# Digital_OUT.net
KiCad netlist of a schematic drawn in Altium Designer
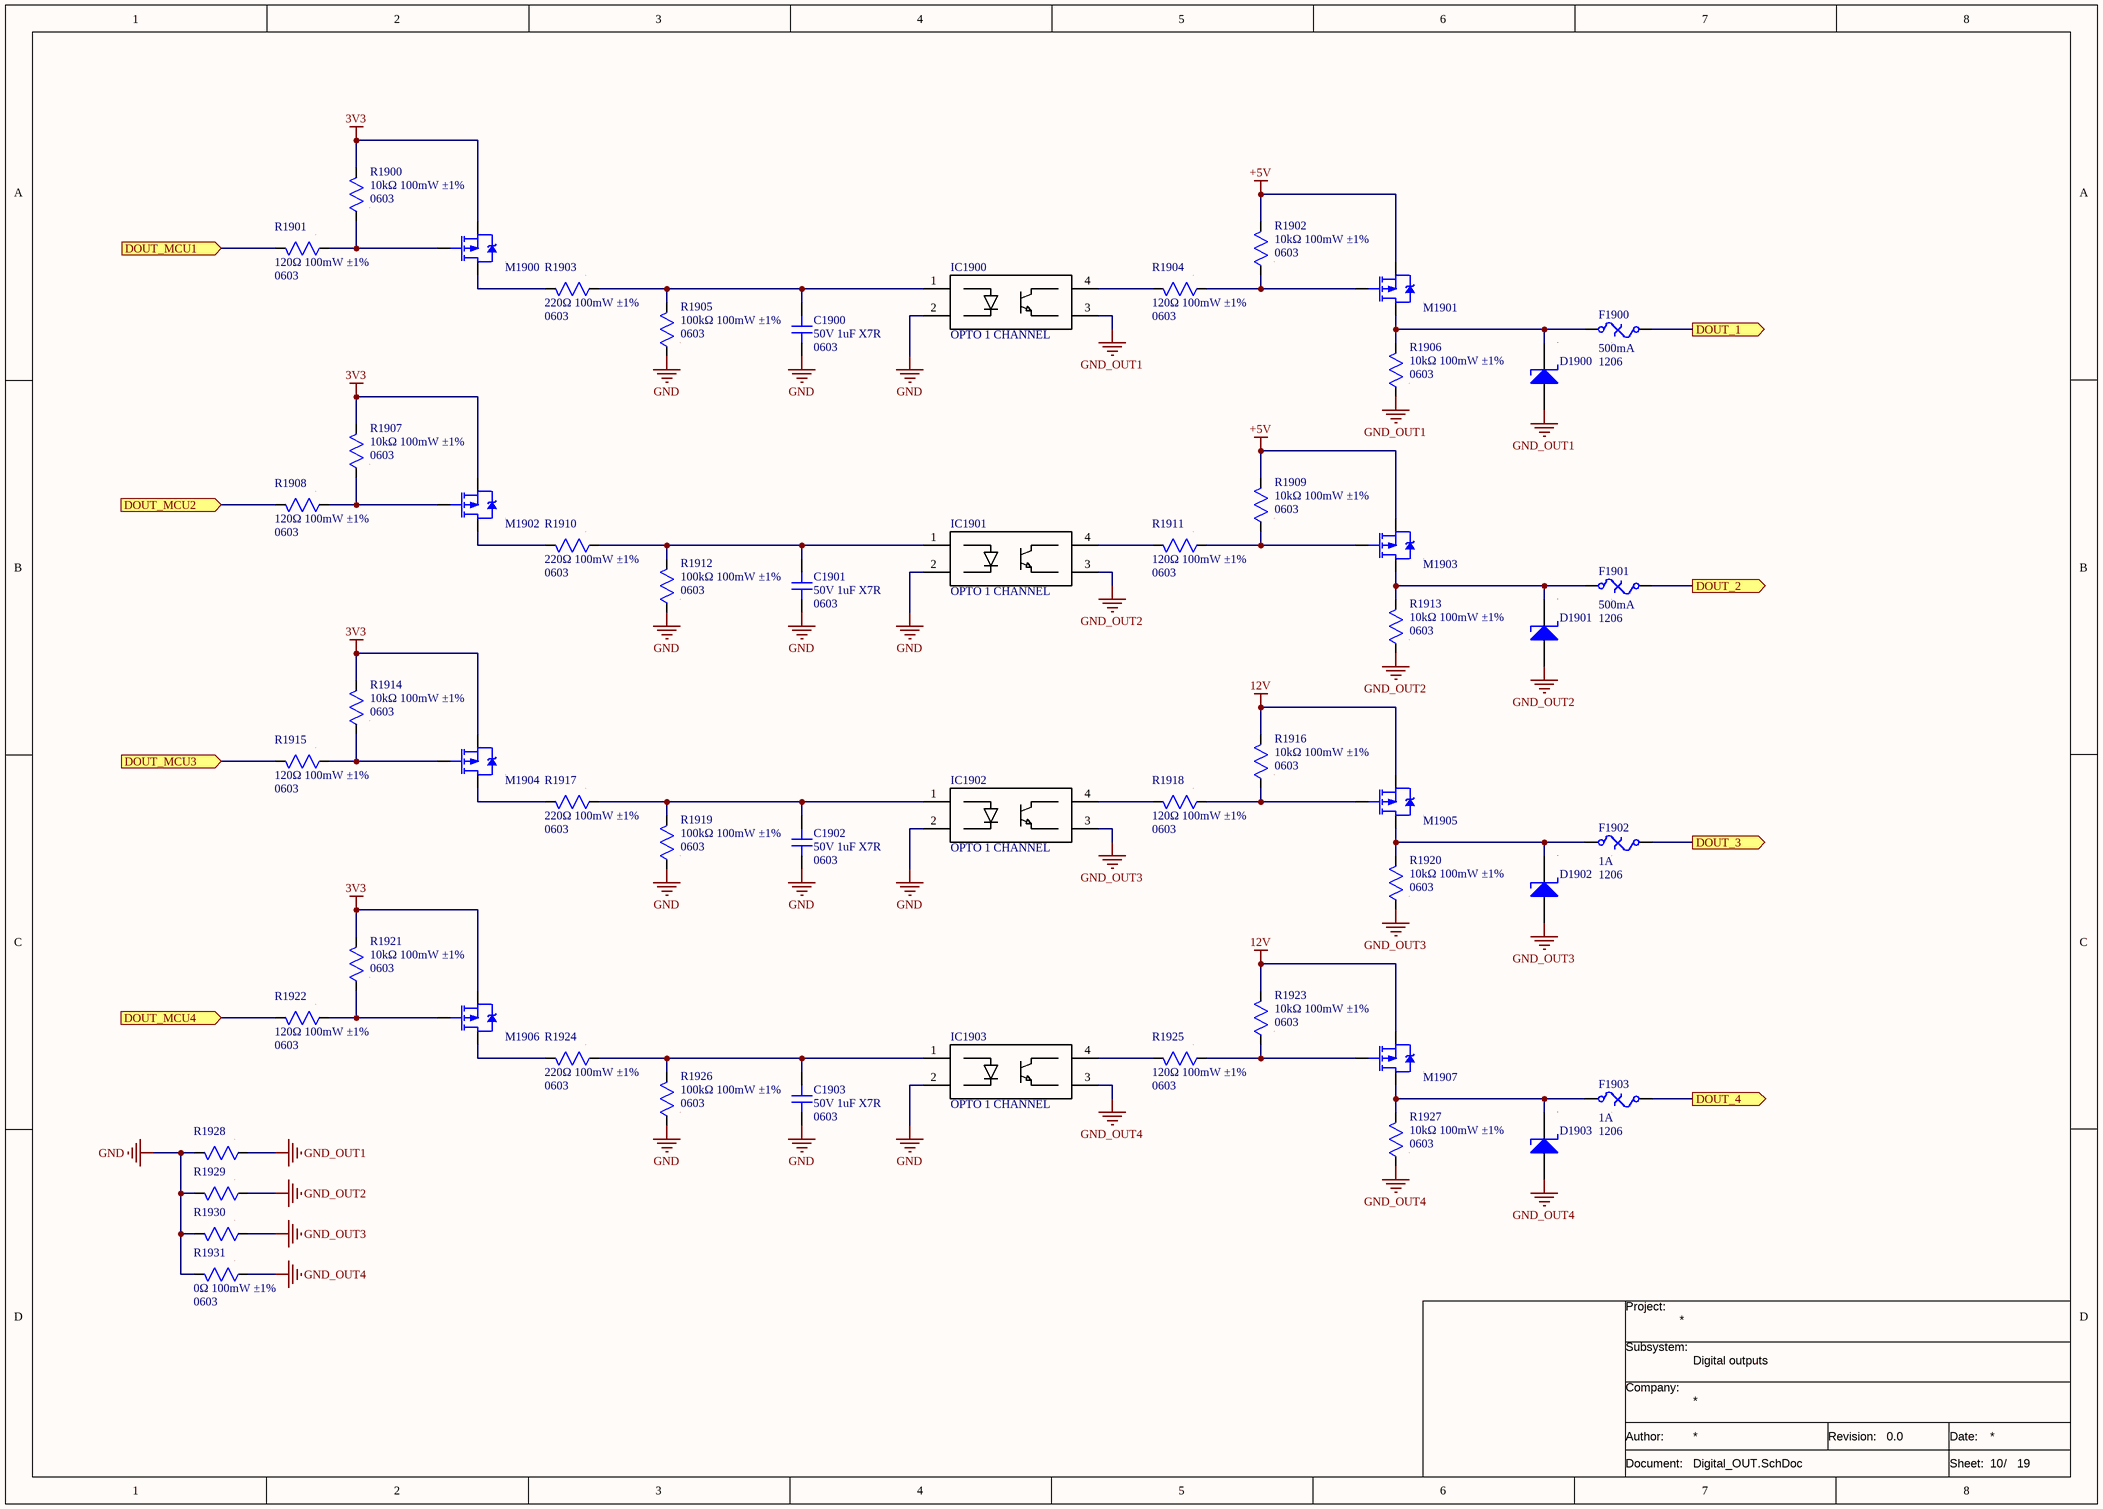
[diagram p0: Digital_OUT.SchDoc]

(export (version "E")
  (design (tool "Eeschema 10.0.6"))
  (components
    (comp (ref "C1900")
      (value "50V 1uF X7R")
      (footprint "CAP SMD 0603")
      (description "Condensadores de cerámica multicapa (MLCC- SMD/SMT) WCAP-CSGP 1uF 50 Vol 10%")
      (fields
        (field (name "PACKAGE") "0603")
        (field (name "MPN") "885012206126")
        (field (name "MANUFACTURER") "Wurth Elektronik")
      )
      (libsource (lib "eUSR_Database") (part "CAP non polarized"))
    )
    (comp (ref "C1901")
      (value "50V 1uF X7R")
      (footprint "CAP SMD 0603")
      (description "Condensadores de cerámica multicapa (MLCC- SMD/SMT) WCAP-CSGP 1uF 50 Vol 10%")
      (fields
        (field (name "PACKAGE") "0603")
        (field (name "MPN") "885012206126")
        (field (name "MANUFACTURER") "Wurth Elektronik")
      )
      (libsource (lib "eUSR_Database") (part "CAP non polarized"))
    )
    (comp (ref "C1902")
      (value "50V 1uF X7R")
      (footprint "CAP SMD 0603")
      (description "Condensadores de cerámica multicapa (MLCC- SMD/SMT) WCAP-CSGP 1uF 50 Vol 10%")
      (fields
        (field (name "PACKAGE") "0603")
        (field (name "MPN") "885012206126")
        (field (name "MANUFACTURER") "Wurth Elektronik")
      )
      (libsource (lib "eUSR_Database") (part "CAP non polarized"))
    )
    (comp (ref "C1903")
      (value "50V 1uF X7R")
      (footprint "CAP SMD 0603")
      (description "Condensadores de cerámica multicapa (MLCC- SMD/SMT) WCAP-CSGP 1uF 50 Vol 10%")
      (fields
        (field (name "PACKAGE") "0603")
        (field (name "MPN") "885012206126")
        (field (name "MANUFACTURER") "Wurth Elektronik")
      )
      (libsource (lib "eUSR_Database") (part "CAP non polarized"))
    )
    (comp (ref "D1900")
      (value "DIODE SCHOTTKY")
      (footprint "DO-214AB")
      (description "Diodos y rectificadores Schottky 3A 60V")
      (fields (field (name "MPN") "MBRS360T3G") (field (name "MANUFACTURER") "onsemi"))
      (libsource (lib "eUSR_Database") (part "DIODE SCHOTTKY"))
    )
    (comp (ref "D1901")
      (value "DIODE SCHOTTKY")
      (footprint "DO-214AB")
      (description "Diodos y rectificadores Schottky 3A 60V")
      (fields (field (name "MPN") "MBRS360T3G") (field (name "MANUFACTURER") "onsemi"))
      (libsource (lib "eUSR_Database") (part "DIODE SCHOTTKY"))
    )
    (comp (ref "D1902")
      (value "DIODE SCHOTTKY")
      (footprint "DO-214AB")
      (description "Diodos y rectificadores Schottky 3A 60V")
      (fields (field (name "MPN") "MBRS360T3G") (field (name "MANUFACTURER") "onsemi"))
      (libsource (lib "eUSR_Database") (part "DIODE SCHOTTKY"))
    )
    (comp (ref "D1903")
      (value "DIODE SCHOTTKY")
      (footprint "DO-214AB")
      (description "Diodos y rectificadores Schottky 3A 60V")
      (fields (field (name "MPN") "MBRS360T3G") (field (name "MANUFACTURER") "onsemi"))
      (libsource (lib "eUSR_Database") (part "DIODE SCHOTTKY"))
    )
    (comp (ref "F1900")
      (value "500mA")
      (footprint "FUSE SMD 1206")
      (description "Fusibles de montaje en superficie 1206 0.5AMPS SMD")
      (fields
        (field (name "PACKAGE") "1206")
        (field (name "MPN") "F1206B0R50FSTR")
        (field (name "MANUFACTURER") "Littelfuse")
      )
      (libsource (lib "eUSR_Database") (part "FUSE"))
    )
    (comp (ref "F1901")
      (value "500mA")
      (footprint "FUSE SMD 1206")
      (description "Fusibles de montaje en superficie 1206 0.5AMPS SMD")
      (fields
        (field (name "PACKAGE") "1206")
        (field (name "MPN") "F1206B0R50FSTR")
        (field (name "MANUFACTURER") "Littelfuse")
      )
      (libsource (lib "eUSR_Database") (part "FUSE"))
    )
    (comp (ref "F1902")
      (value "1A")
      (footprint "FUSE SMD 1206")
      (description "Fusibles de montaje en superficie 63V 1A FA HALIDE FREE SLIM")
      (fields
        (field (name "PACKAGE") "1206")
        (field (name "MPN") "0466001.NRHF")
        (field (name "MANUFACTURER") "Littelfuse")
      )
      (libsource (lib "eUSR_Database") (part "FUSE"))
    )
    (comp (ref "F1903")
      (value "1A")
      (footprint "FUSE SMD 1206")
      (description "Fusibles de montaje en superficie 63V 1A FA HALIDE FREE SLIM")
      (fields
        (field (name "PACKAGE") "1206")
        (field (name "MPN") "0466001.NRHF")
        (field (name "MANUFACTURER") "Littelfuse")
      )
      (libsource (lib "eUSR_Database") (part "FUSE"))
    )
    (comp (ref "IC1900")
      (value "OPTO 1 CHANNEL")
      (footprint "SOIC-4")
      (description "Optoacopladores para salidas de transistores Automotive DC-input transistor-output s")
      (fields (field (name "MPN") "ISOM8110DFHRQ1") (field (name "MANUFACTURER") "Texas Instruments"))
      (libsource (lib "eUSR_Database") (part "OPTO 1 CHANNEL"))
    )
    (comp (ref "IC1901")
      (value "OPTO 1 CHANNEL")
      (footprint "SOIC-4")
      (description "Optoacopladores para salidas de transistores Automotive DC-input transistor-output s")
      (fields (field (name "MPN") "ISOM8110DFHRQ1") (field (name "MANUFACTURER") "Texas Instruments"))
      (libsource (lib "eUSR_Database") (part "OPTO 1 CHANNEL"))
    )
    (comp (ref "IC1902")
      (value "OPTO 1 CHANNEL")
      (footprint "SOIC-4")
      (description "Optoacopladores para salidas de transistores Automotive DC-input transistor-output s")
      (fields (field (name "MPN") "ISOM8110DFHRQ1") (field (name "MANUFACTURER") "Texas Instruments"))
      (libsource (lib "eUSR_Database") (part "OPTO 1 CHANNEL"))
    )
    (comp (ref "IC1903")
      (value "OPTO 1 CHANNEL")
      (footprint "SOIC-4")
      (description "Optoacopladores para salidas de transistores Automotive DC-input transistor-output s")
      (fields (field (name "MPN") "ISOM8110DFHRQ1") (field (name "MANUFACTURER") "Texas Instruments"))
      (libsource (lib "eUSR_Database") (part "OPTO 1 CHANNEL"))
    )
    (comp (ref "M1900")
      (value "MOSFET P")
      (footprint "SOT-23")
      (description "MOSFET -30V Vds 20V Vgs SOT-23")
      (fields (field (name "MPN") "SI2303CDS-T1-GE3") (field (name "MANUFACTURER") "Vishay Semiconductors"))
      (libsource (lib "eUSR_Database") (part "MOSFET P"))
    )
    (comp (ref "M1901")
      (value "MOSFET P")
      (footprint "SOT-23")
      (description "MOSFET -30V Vds 20V Vgs SOT-23")
      (fields (field (name "MPN") "SI2303CDS-T1-GE3") (field (name "MANUFACTURER") "Vishay Semiconductors"))
      (libsource (lib "eUSR_Database") (part "MOSFET P"))
    )
    (comp (ref "M1902")
      (value "MOSFET P")
      (footprint "SOT-23")
      (description "MOSFET -30V Vds 20V Vgs SOT-23")
      (fields (field (name "MPN") "SI2303CDS-T1-GE3") (field (name "MANUFACTURER") "Vishay Semiconductors"))
      (libsource (lib "eUSR_Database") (part "MOSFET P"))
    )
    (comp (ref "M1903")
      (value "MOSFET P")
      (footprint "SOT-23")
      (description "MOSFET -30V Vds 20V Vgs SOT-23")
      (fields (field (name "MPN") "SI2303CDS-T1-GE3") (field (name "MANUFACTURER") "Vishay Semiconductors"))
      (libsource (lib "eUSR_Database") (part "MOSFET P"))
    )
    (comp (ref "M1904")
      (value "MOSFET P")
      (footprint "SOT-23")
      (description "MOSFET -30V Vds 20V Vgs SOT-23")
      (fields (field (name "MPN") "SI2303CDS-T1-GE3") (field (name "MANUFACTURER") "Vishay Semiconductors"))
      (libsource (lib "eUSR_Database") (part "MOSFET P"))
    )
    (comp (ref "M1905")
      (value "MOSFET P")
      (footprint "SOT-23")
      (description "MOSFET -30V Vds 20V Vgs SOT-23")
      (fields (field (name "MPN") "SI2303CDS-T1-GE3") (field (name "MANUFACTURER") "Vishay Semiconductors"))
      (libsource (lib "eUSR_Database") (part "MOSFET P"))
    )
    (comp (ref "M1906")
      (value "MOSFET P")
      (footprint "SOT-23")
      (description "MOSFET -30V Vds 20V Vgs SOT-23")
      (fields (field (name "MPN") "SI2303CDS-T1-GE3") (field (name "MANUFACTURER") "Vishay Semiconductors"))
      (libsource (lib "eUSR_Database") (part "MOSFET P"))
    )
    (comp (ref "M1907")
      (value "MOSFET P")
      (footprint "SOT-23")
      (description "MOSFET -30V Vds 20V Vgs SOT-23")
      (fields (field (name "MPN") "SI2303CDS-T1-GE3") (field (name "MANUFACTURER") "Vishay Semiconductors"))
      (libsource (lib "eUSR_Database") (part "MOSFET P"))
    )
    (comp (ref "R1900")
      (value "10kΩ 100mW ±1%")
      (footprint "RES SMD 0603")
      (description "Resistores de película gruesa - SMD WRIS-RSKS 10 kOhms 1 % 0.1 W 0603 AEC-Q200")
      (fields
        (field (name "PACKAGE") "0603")
        (field (name "MPN") "560112116005")
        (field (name "MANUFACTURER") "Wurth Elektronik")
      )
      (libsource (lib "eUSR_Database") (part "RES"))
    )
    (comp (ref "R1901")
      (value "120Ω 100mW ±1%")
      (footprint "RES SMD 0603")
      (description "Resistores de película gruesa - SMD WRIS-RSKS 120 Ohms 1 % 0.1 W 0603 AEC-Q200")
      (fields
        (field (name "PACKAGE") "0603")
        (field (name "MPN") "560112116119")
        (field (name "MANUFACTURER") "Wurth Elektronik")
      )
      (libsource (lib "eUSR_Database") (part "RES"))
    )
    (comp (ref "R1902")
      (value "10kΩ 100mW ±1%")
      (footprint "RES SMD 0603")
      (description "Resistores de película gruesa - SMD WRIS-RSKS 10 kOhms 1 % 0.1 W 0603 AEC-Q200")
      (fields
        (field (name "PACKAGE") "0603")
        (field (name "MPN") "560112116005")
        (field (name "MANUFACTURER") "Wurth Elektronik")
      )
      (libsource (lib "eUSR_Database") (part "RES"))
    )
    (comp (ref "R1903")
      (value "220Ω 100mW ±1%")
      (footprint "RES SMD 0603")
      (description "Resistores de película gruesa - SMD WRIS-RSKS 220 Ohms 1 % 0.1 W 0603 AEC-Q200")
      (fields
        (field (name "PACKAGE") "0603")
        (field (name "MPN") "560112116126")
        (field (name "MANUFACTURER") "Wurth Elektronik")
      )
      (libsource (lib "eUSR_Database") (part "RES"))
    )
    (comp (ref "R1904")
      (value "120Ω 100mW ±1%")
      (footprint "RES SMD 0603")
      (description "Resistores de película gruesa - SMD WRIS-RSKS 120 Ohms 1 % 0.1 W 0603 AEC-Q200")
      (fields
        (field (name "PACKAGE") "0603")
        (field (name "MPN") "560112116119")
        (field (name "MANUFACTURER") "Wurth Elektronik")
      )
      (libsource (lib "eUSR_Database") (part "RES"))
    )
    (comp (ref "R1905")
      (value "100kΩ 100mW ±1%")
      (footprint "RES SMD 0603")
      (description "Thick Film Resistors WRIS-RSKS 100 kOhms 1 % 0.1 W 0603 AEC-Q200")
      (fields
        (field (name "PACKAGE") "0603")
        (field (name "MPN") "560112116004")
        (field (name "MANUFACTURER") "Wurth Elektronik")
      )
      (libsource (lib "eUSR_Database") (part "RES"))
    )
    (comp (ref "R1906")
      (value "10kΩ 100mW ±1%")
      (footprint "RES SMD 0603")
      (description "Resistores de película gruesa - SMD WRIS-RSKS 10 kOhms 1 % 0.1 W 0603 AEC-Q200")
      (fields
        (field (name "PACKAGE") "0603")
        (field (name "MPN") "560112116005")
        (field (name "MANUFACTURER") "Wurth Elektronik")
      )
      (libsource (lib "eUSR_Database") (part "RES"))
    )
    (comp (ref "R1907")
      (value "10kΩ 100mW ±1%")
      (footprint "RES SMD 0603")
      (description "Resistores de película gruesa - SMD WRIS-RSKS 10 kOhms 1 % 0.1 W 0603 AEC-Q200")
      (fields
        (field (name "PACKAGE") "0603")
        (field (name "MPN") "560112116005")
        (field (name "MANUFACTURER") "Wurth Elektronik")
      )
      (libsource (lib "eUSR_Database") (part "RES"))
    )
    (comp (ref "R1908")
      (value "120Ω 100mW ±1%")
      (footprint "RES SMD 0603")
      (description "Resistores de película gruesa - SMD WRIS-RSKS 120 Ohms 1 % 0.1 W 0603 AEC-Q200")
      (fields
        (field (name "PACKAGE") "0603")
        (field (name "MPN") "560112116119")
        (field (name "MANUFACTURER") "Wurth Elektronik")
      )
      (libsource (lib "eUSR_Database") (part "RES"))
    )
    (comp (ref "R1909")
      (value "10kΩ 100mW ±1%")
      (footprint "RES SMD 0603")
      (description "Resistores de película gruesa - SMD WRIS-RSKS 10 kOhms 1 % 0.1 W 0603 AEC-Q200")
      (fields
        (field (name "PACKAGE") "0603")
        (field (name "MPN") "560112116005")
        (field (name "MANUFACTURER") "Wurth Elektronik")
      )
      (libsource (lib "eUSR_Database") (part "RES"))
    )
    (comp (ref "R1910")
      (value "220Ω 100mW ±1%")
      (footprint "RES SMD 0603")
      (description "Resistores de película gruesa - SMD WRIS-RSKS 220 Ohms 1 % 0.1 W 0603 AEC-Q200")
      (fields
        (field (name "PACKAGE") "0603")
        (field (name "MPN") "560112116126")
        (field (name "MANUFACTURER") "Wurth Elektronik")
      )
      (libsource (lib "eUSR_Database") (part "RES"))
    )
    (comp (ref "R1911")
      (value "120Ω 100mW ±1%")
      (footprint "RES SMD 0603")
      (description "Resistores de película gruesa - SMD WRIS-RSKS 120 Ohms 1 % 0.1 W 0603 AEC-Q200")
      (fields
        (field (name "PACKAGE") "0603")
        (field (name "MPN") "560112116119")
        (field (name "MANUFACTURER") "Wurth Elektronik")
      )
      (libsource (lib "eUSR_Database") (part "RES"))
    )
    (comp (ref "R1912")
      (value "100kΩ 100mW ±1%")
      (footprint "RES SMD 0603")
      (description "Thick Film Resistors WRIS-RSKS 100 kOhms 1 % 0.1 W 0603 AEC-Q200")
      (fields
        (field (name "PACKAGE") "0603")
        (field (name "MPN") "560112116004")
        (field (name "MANUFACTURER") "Wurth Elektronik")
      )
      (libsource (lib "eUSR_Database") (part "RES"))
    )
    (comp (ref "R1913")
      (value "10kΩ 100mW ±1%")
      (footprint "RES SMD 0603")
      (description "Resistores de película gruesa - SMD WRIS-RSKS 10 kOhms 1 % 0.1 W 0603 AEC-Q200")
      (fields
        (field (name "PACKAGE") "0603")
        (field (name "MPN") "560112116005")
        (field (name "MANUFACTURER") "Wurth Elektronik")
      )
      (libsource (lib "eUSR_Database") (part "RES"))
    )
    (comp (ref "R1914")
      (value "10kΩ 100mW ±1%")
      (footprint "RES SMD 0603")
      (description "Resistores de película gruesa - SMD WRIS-RSKS 10 kOhms 1 % 0.1 W 0603 AEC-Q200")
      (fields
        (field (name "PACKAGE") "0603")
        (field (name "MPN") "560112116005")
        (field (name "MANUFACTURER") "Wurth Elektronik")
      )
      (libsource (lib "eUSR_Database") (part "RES"))
    )
    (comp (ref "R1915")
      (value "120Ω 100mW ±1%")
      (footprint "RES SMD 0603")
      (description "Resistores de película gruesa - SMD WRIS-RSKS 120 Ohms 1 % 0.1 W 0603 AEC-Q200")
      (fields
        (field (name "PACKAGE") "0603")
        (field (name "MPN") "560112116119")
        (field (name "MANUFACTURER") "Wurth Elektronik")
      )
      (libsource (lib "eUSR_Database") (part "RES"))
    )
    (comp (ref "R1916")
      (value "10kΩ 100mW ±1%")
      (footprint "RES SMD 0603")
      (description "Resistores de película gruesa - SMD WRIS-RSKS 10 kOhms 1 % 0.1 W 0603 AEC-Q200")
      (fields
        (field (name "PACKAGE") "0603")
        (field (name "MPN") "560112116005")
        (field (name "MANUFACTURER") "Wurth Elektronik")
      )
      (libsource (lib "eUSR_Database") (part "RES"))
    )
    (comp (ref "R1917")
      (value "220Ω 100mW ±1%")
      (footprint "RES SMD 0603")
      (description "Resistores de película gruesa - SMD WRIS-RSKS 220 Ohms 1 % 0.1 W 0603 AEC-Q200")
      (fields
        (field (name "PACKAGE") "0603")
        (field (name "MPN") "560112116126")
        (field (name "MANUFACTURER") "Wurth Elektronik")
      )
      (libsource (lib "eUSR_Database") (part "RES"))
    )
    (comp (ref "R1918")
      (value "120Ω 100mW ±1%")
      (footprint "RES SMD 0603")
      (description "Resistores de película gruesa - SMD WRIS-RSKS 120 Ohms 1 % 0.1 W 0603 AEC-Q200")
      (fields
        (field (name "PACKAGE") "0603")
        (field (name "MPN") "560112116119")
        (field (name "MANUFACTURER") "Wurth Elektronik")
      )
      (libsource (lib "eUSR_Database") (part "RES"))
    )
    (comp (ref "R1919")
      (value "100kΩ 100mW ±1%")
      (footprint "RES SMD 0603")
      (description "Thick Film Resistors WRIS-RSKS 100 kOhms 1 % 0.1 W 0603 AEC-Q200")
      (fields
        (field (name "PACKAGE") "0603")
        (field (name "MPN") "560112116004")
        (field (name "MANUFACTURER") "Wurth Elektronik")
      )
      (libsource (lib "eUSR_Database") (part "RES"))
    )
    (comp (ref "R1920")
      (value "10kΩ 100mW ±1%")
      (footprint "RES SMD 0603")
      (description "Resistores de película gruesa - SMD WRIS-RSKS 10 kOhms 1 % 0.1 W 0603 AEC-Q200")
      (fields
        (field (name "PACKAGE") "0603")
        (field (name "MPN") "560112116005")
        (field (name "MANUFACTURER") "Wurth Elektronik")
      )
      (libsource (lib "eUSR_Database") (part "RES"))
    )
    (comp (ref "R1921")
      (value "10kΩ 100mW ±1%")
      (footprint "RES SMD 0603")
      (description "Resistores de película gruesa - SMD WRIS-RSKS 10 kOhms 1 % 0.1 W 0603 AEC-Q200")
      (fields
        (field (name "PACKAGE") "0603")
        (field (name "MPN") "560112116005")
        (field (name "MANUFACTURER") "Wurth Elektronik")
      )
      (libsource (lib "eUSR_Database") (part "RES"))
    )
    (comp (ref "R1922")
      (value "120Ω 100mW ±1%")
      (footprint "RES SMD 0603")
      (description "Resistores de película gruesa - SMD WRIS-RSKS 120 Ohms 1 % 0.1 W 0603 AEC-Q200")
      (fields
        (field (name "PACKAGE") "0603")
        (field (name "MPN") "560112116119")
        (field (name "MANUFACTURER") "Wurth Elektronik")
      )
      (libsource (lib "eUSR_Database") (part "RES"))
    )
    (comp (ref "R1923")
      (value "10kΩ 100mW ±1%")
      (footprint "RES SMD 0603")
      (description "Resistores de película gruesa - SMD WRIS-RSKS 10 kOhms 1 % 0.1 W 0603 AEC-Q200")
      (fields
        (field (name "PACKAGE") "0603")
        (field (name "MPN") "560112116005")
        (field (name "MANUFACTURER") "Wurth Elektronik")
      )
      (libsource (lib "eUSR_Database") (part "RES"))
    )
    (comp (ref "R1924")
      (value "220Ω 100mW ±1%")
      (footprint "RES SMD 0603")
      (description "Resistores de película gruesa - SMD WRIS-RSKS 220 Ohms 1 % 0.1 W 0603 AEC-Q200")
      (fields
        (field (name "PACKAGE") "0603")
        (field (name "MPN") "560112116126")
        (field (name "MANUFACTURER") "Wurth Elektronik")
      )
      (libsource (lib "eUSR_Database") (part "RES"))
    )
    (comp (ref "R1925")
      (value "120Ω 100mW ±1%")
      (footprint "RES SMD 0603")
      (description "Resistores de película gruesa - SMD WRIS-RSKS 120 Ohms 1 % 0.1 W 0603 AEC-Q200")
      (fields
        (field (name "PACKAGE") "0603")
        (field (name "MPN") "560112116119")
        (field (name "MANUFACTURER") "Wurth Elektronik")
      )
      (libsource (lib "eUSR_Database") (part "RES"))
    )
    (comp (ref "R1926")
      (value "100kΩ 100mW ±1%")
      (footprint "RES SMD 0603")
      (description "Thick Film Resistors WRIS-RSKS 100 kOhms 1 % 0.1 W 0603 AEC-Q200")
      (fields
        (field (name "PACKAGE") "0603")
        (field (name "MPN") "560112116004")
        (field (name "MANUFACTURER") "Wurth Elektronik")
      )
      (libsource (lib "eUSR_Database") (part "RES"))
    )
    (comp (ref "R1927")
      (value "10kΩ 100mW ±1%")
      (footprint "RES SMD 0603")
      (description "Resistores de película gruesa - SMD WRIS-RSKS 10 kOhms 1 % 0.1 W 0603 AEC-Q200")
      (fields
        (field (name "PACKAGE") "0603")
        (field (name "MPN") "560112116005")
        (field (name "MANUFACTURER") "Wurth Elektronik")
      )
      (libsource (lib "eUSR_Database") (part "RES"))
    )
    (comp (ref "R1928")
      (value "RES")
      (footprint "RES SMD 0603")
      (description "Resistores de película gruesa - SMD WRIS-RSKS <0.05 Ohms 0.1 W Jumper 0603 AEC-Q200")
      (fields (field (name "MPN") "560112116001") (field (name "MANUFACTURER") "Wurth Elektronik"))
      (libsource (lib "eUSR_Database") (part "RES"))
    )
    (comp (ref "R1929")
      (value "RES")
      (footprint "RES SMD 0603")
      (description "Resistores de película gruesa - SMD WRIS-RSKS <0.05 Ohms 0.1 W Jumper 0603 AEC-Q200")
      (fields (field (name "MPN") "560112116001") (field (name "MANUFACTURER") "Wurth Elektronik"))
      (libsource (lib "eUSR_Database") (part "RES"))
    )
    (comp (ref "R1930")
      (value "RES")
      (footprint "RES SMD 0603")
      (description "Resistores de película gruesa - SMD WRIS-RSKS <0.05 Ohms 0.1 W Jumper 0603 AEC-Q200")
      (fields (field (name "MPN") "560112116001") (field (name "MANUFACTURER") "Wurth Elektronik"))
      (libsource (lib "eUSR_Database") (part "RES"))
    )
    (comp (ref "R1931")
      (value "0Ω 100mW ±1%")
      (footprint "RES SMD 0603")
      (description "Resistores de película gruesa - SMD WRIS-RSKS <0.05 Ohms 0.1 W Jumper 0603 AEC-Q200")
      (fields
        (field (name "PACKAGE") "0603")
        (field (name "MPN") "560112116001")
        (field (name "MANUFACTURER") "Wurth Elektronik")
      )
      (libsource (lib "eUSR_Database") (part "RES"))
    )
  )
  (nets
    (net (code "1") (name "+5V") (class "Default")
      (node (ref "M1901") (pin "2") (pinfunction "S_2") (pintype "passive"))
      (node (ref "M1903") (pin "2") (pinfunction "S_2") (pintype "passive"))
      (node (ref "R1902") (pin "2") (pinfunction "2_2") (pintype "passive"))
      (node (ref "R1909") (pin "2") (pinfunction "2_2") (pintype "passive"))
    )
    (net (code "2") (name "/DOUT_1") (class "Default")
      (node (ref "F1900") (pin "2") (pinfunction "2_2") (pintype "passive"))
    )
    (net (code "3") (name "/DOUT_2") (class "Default")
      (node (ref "F1901") (pin "2") (pinfunction "2_2") (pintype "passive"))
    )
    (net (code "4") (name "/DOUT_3") (class "Default")
      (node (ref "F1902") (pin "2") (pinfunction "2_2") (pintype "passive"))
    )
    (net (code "5") (name "/DOUT_4") (class "Default")
      (node (ref "F1903") (pin "2") (pinfunction "2_2") (pintype "passive"))
    )
    (net (code "6") (name "/DOUT_MCU1") (class "Default")
      (node (ref "R1901") (pin "2") (pinfunction "2_2") (pintype "passive"))
    )
    (net (code "7") (name "/DOUT_MCU2") (class "Default")
      (node (ref "R1908") (pin "2") (pinfunction "2_2") (pintype "passive"))
    )
    (net (code "8") (name "/DOUT_MCU3") (class "Default")
      (node (ref "R1915") (pin "2") (pinfunction "2_2") (pintype "passive"))
    )
    (net (code "9") (name "/DOUT_MCU4") (class "Default")
      (node (ref "R1922") (pin "2") (pinfunction "2_2") (pintype "passive"))
    )
    (net (code "10") (name "3V3") (class "Default")
      (node (ref "M1900") (pin "2") (pinfunction "S_2") (pintype "passive"))
      (node (ref "M1902") (pin "2") (pinfunction "S_2") (pintype "passive"))
      (node (ref "M1904") (pin "2") (pinfunction "S_2") (pintype "passive"))
      (node (ref "M1906") (pin "2") (pinfunction "S_2") (pintype "passive"))
      (node (ref "R1900") (pin "2") (pinfunction "2_2") (pintype "passive"))
      (node (ref "R1907") (pin "2") (pinfunction "2_2") (pintype "passive"))
      (node (ref "R1914") (pin "2") (pinfunction "2_2") (pintype "passive"))
      (node (ref "R1921") (pin "2") (pinfunction "2_2") (pintype "passive"))
    )
    (net (code "11") (name "12V") (class "Default")
      (node (ref "M1905") (pin "2") (pinfunction "S_2") (pintype "passive"))
      (node (ref "M1907") (pin "2") (pinfunction "S_2") (pintype "passive"))
      (node (ref "R1916") (pin "2") (pinfunction "2_2") (pintype "passive"))
      (node (ref "R1923") (pin "2") (pinfunction "2_2") (pintype "passive"))
    )
    (net (code "12") (name "GND") (class "Default")
      (node (ref "C1900") (pin "2") (pinfunction "2_2") (pintype "passive"))
      (node (ref "C1901") (pin "2") (pinfunction "2_2") (pintype "passive"))
      (node (ref "C1902") (pin "2") (pinfunction "2_2") (pintype "passive"))
      (node (ref "C1903") (pin "2") (pinfunction "2_2") (pintype "passive"))
      (node (ref "IC1900") (pin "2") (pinfunction "K_1_2") (pintype "passive"))
      (node (ref "IC1901") (pin "2") (pinfunction "K_1_2") (pintype "passive"))
      (node (ref "IC1902") (pin "2") (pinfunction "K_1_2") (pintype "passive"))
      (node (ref "IC1903") (pin "2") (pinfunction "K_1_2") (pintype "passive"))
      (node (ref "R1905") (pin "1") (pinfunction "1_1") (pintype "passive"))
      (node (ref "R1912") (pin "1") (pinfunction "1_1") (pintype "passive"))
      (node (ref "R1919") (pin "1") (pinfunction "1_1") (pintype "passive"))
      (node (ref "R1926") (pin "1") (pinfunction "1_1") (pintype "passive"))
      (node (ref "R1928") (pin "2") (pinfunction "2_2") (pintype "passive"))
      (node (ref "R1929") (pin "2") (pinfunction "2_2") (pintype "passive"))
      (node (ref "R1930") (pin "2") (pinfunction "2_2") (pintype "passive"))
      (node (ref "R1931") (pin "2") (pinfunction "2_2") (pintype "passive"))
    )
    (net (code "13") (name "GND_OUT1") (class "Default")
      (node (ref "D1900") (pin "A") (pinfunction "A_A") (pintype "passive"))
      (node (ref "IC1900") (pin "3") (pinfunction "E_1_3") (pintype "passive"))
      (node (ref "R1906") (pin "1") (pinfunction "1_1") (pintype "passive"))
      (node (ref "R1928") (pin "1") (pinfunction "1_1") (pintype "passive"))
    )
    (net (code "14") (name "GND_OUT2") (class "Default")
      (node (ref "D1901") (pin "A") (pinfunction "A_A") (pintype "passive"))
      (node (ref "IC1901") (pin "3") (pinfunction "E_1_3") (pintype "passive"))
      (node (ref "R1913") (pin "1") (pinfunction "1_1") (pintype "passive"))
      (node (ref "R1929") (pin "1") (pinfunction "1_1") (pintype "passive"))
    )
    (net (code "15") (name "GND_OUT3") (class "Default")
      (node (ref "D1902") (pin "A") (pinfunction "A_A") (pintype "passive"))
      (node (ref "IC1902") (pin "3") (pinfunction "E_1_3") (pintype "passive"))
      (node (ref "R1920") (pin "1") (pinfunction "1_1") (pintype "passive"))
      (node (ref "R1930") (pin "1") (pinfunction "1_1") (pintype "passive"))
    )
    (net (code "16") (name "GND_OUT4") (class "Default")
      (node (ref "D1903") (pin "A") (pinfunction "A_A") (pintype "passive"))
      (node (ref "IC1903") (pin "3") (pinfunction "E_1_3") (pintype "passive"))
      (node (ref "R1927") (pin "1") (pinfunction "1_1") (pintype "passive"))
      (node (ref "R1931") (pin "1") (pinfunction "1_1") (pintype "passive"))
    )
    (net (code "17") (name "Net-(IC1900-A_1)") (class "Default")
      (node (ref "C1900") (pin "1") (pinfunction "1_1") (pintype "passive"))
      (node (ref "IC1900") (pin "1") (pinfunction "A_1_1") (pintype "passive"))
      (node (ref "R1903") (pin "1") (pinfunction "1_1") (pintype "passive"))
      (node (ref "R1905") (pin "2") (pinfunction "2_2") (pintype "passive"))
    )
    (net (code "18") (name "Net-(IC1900-C_1)") (class "Default")
      (node (ref "IC1900") (pin "4") (pinfunction "C_1_4") (pintype "passive"))
      (node (ref "R1904") (pin "2") (pinfunction "2_2") (pintype "passive"))
    )
    (net (code "19") (name "Net-(IC1901-A_1)") (class "Default")
      (node (ref "C1901") (pin "1") (pinfunction "1_1") (pintype "passive"))
      (node (ref "IC1901") (pin "1") (pinfunction "A_1_1") (pintype "passive"))
      (node (ref "R1910") (pin "1") (pinfunction "1_1") (pintype "passive"))
      (node (ref "R1912") (pin "2") (pinfunction "2_2") (pintype "passive"))
    )
    (net (code "20") (name "Net-(IC1901-C_1)") (class "Default")
      (node (ref "IC1901") (pin "4") (pinfunction "C_1_4") (pintype "passive"))
      (node (ref "R1911") (pin "2") (pinfunction "2_2") (pintype "passive"))
    )
    (net (code "21") (name "Net-(IC1902-A_1)") (class "Default")
      (node (ref "C1902") (pin "1") (pinfunction "1_1") (pintype "passive"))
      (node (ref "IC1902") (pin "1") (pinfunction "A_1_1") (pintype "passive"))
      (node (ref "R1917") (pin "1") (pinfunction "1_1") (pintype "passive"))
      (node (ref "R1919") (pin "2") (pinfunction "2_2") (pintype "passive"))
    )
    (net (code "22") (name "Net-(IC1902-C_1)") (class "Default")
      (node (ref "IC1902") (pin "4") (pinfunction "C_1_4") (pintype "passive"))
      (node (ref "R1918") (pin "2") (pinfunction "2_2") (pintype "passive"))
    )
    (net (code "23") (name "Net-(IC1903-A_1)") (class "Default")
      (node (ref "C1903") (pin "1") (pinfunction "1_1") (pintype "passive"))
      (node (ref "IC1903") (pin "1") (pinfunction "A_1_1") (pintype "passive"))
      (node (ref "R1924") (pin "1") (pinfunction "1_1") (pintype "passive"))
      (node (ref "R1926") (pin "2") (pinfunction "2_2") (pintype "passive"))
    )
    (net (code "24") (name "Net-(IC1903-C_1)") (class "Default")
      (node (ref "IC1903") (pin "4") (pinfunction "C_1_4") (pintype "passive"))
      (node (ref "R1925") (pin "2") (pinfunction "2_2") (pintype "passive"))
    )
    (net (code "25") (name "Net-(M1900-D)") (class "Default")
      (node (ref "M1900") (pin "3") (pinfunction "D_3") (pintype "passive"))
      (node (ref "R1903") (pin "2") (pinfunction "2_2") (pintype "passive"))
    )
    (net (code "26") (name "Net-(M1900-G)") (class "Default")
      (node (ref "M1900") (pin "1") (pinfunction "G_1") (pintype "passive"))
      (node (ref "R1900") (pin "1") (pinfunction "1_1") (pintype "passive"))
      (node (ref "R1901") (pin "1") (pinfunction "1_1") (pintype "passive"))
    )
    (net (code "27") (name "Net-(M1901-D)") (class "Default")
      (node (ref "D1900") (pin "K") (pinfunction "K_K") (pintype "passive"))
      (node (ref "F1900") (pin "1") (pinfunction "1_1") (pintype "passive"))
      (node (ref "M1901") (pin "3") (pinfunction "D_3") (pintype "passive"))
      (node (ref "R1906") (pin "2") (pinfunction "2_2") (pintype "passive"))
    )
    (net (code "28") (name "Net-(M1901-G)") (class "Default")
      (node (ref "M1901") (pin "1") (pinfunction "G_1") (pintype "passive"))
      (node (ref "R1902") (pin "1") (pinfunction "1_1") (pintype "passive"))
      (node (ref "R1904") (pin "1") (pinfunction "1_1") (pintype "passive"))
    )
    (net (code "29") (name "Net-(M1902-D)") (class "Default")
      (node (ref "M1902") (pin "3") (pinfunction "D_3") (pintype "passive"))
      (node (ref "R1910") (pin "2") (pinfunction "2_2") (pintype "passive"))
    )
    (net (code "30") (name "Net-(M1902-G)") (class "Default")
      (node (ref "M1902") (pin "1") (pinfunction "G_1") (pintype "passive"))
      (node (ref "R1907") (pin "1") (pinfunction "1_1") (pintype "passive"))
      (node (ref "R1908") (pin "1") (pinfunction "1_1") (pintype "passive"))
    )
    (net (code "31") (name "Net-(M1903-D)") (class "Default")
      (node (ref "D1901") (pin "K") (pinfunction "K_K") (pintype "passive"))
      (node (ref "F1901") (pin "1") (pinfunction "1_1") (pintype "passive"))
      (node (ref "M1903") (pin "3") (pinfunction "D_3") (pintype "passive"))
      (node (ref "R1913") (pin "2") (pinfunction "2_2") (pintype "passive"))
    )
    (net (code "32") (name "Net-(M1903-G)") (class "Default")
      (node (ref "M1903") (pin "1") (pinfunction "G_1") (pintype "passive"))
      (node (ref "R1909") (pin "1") (pinfunction "1_1") (pintype "passive"))
      (node (ref "R1911") (pin "1") (pinfunction "1_1") (pintype "passive"))
    )
    (net (code "33") (name "Net-(M1904-D)") (class "Default")
      (node (ref "M1904") (pin "3") (pinfunction "D_3") (pintype "passive"))
      (node (ref "R1917") (pin "2") (pinfunction "2_2") (pintype "passive"))
    )
    (net (code "34") (name "Net-(M1904-G)") (class "Default")
      (node (ref "M1904") (pin "1") (pinfunction "G_1") (pintype "passive"))
      (node (ref "R1914") (pin "1") (pinfunction "1_1") (pintype "passive"))
      (node (ref "R1915") (pin "1") (pinfunction "1_1") (pintype "passive"))
    )
    (net (code "35") (name "Net-(M1905-D)") (class "Default")
      (node (ref "D1902") (pin "K") (pinfunction "K_K") (pintype "passive"))
      (node (ref "F1902") (pin "1") (pinfunction "1_1") (pintype "passive"))
      (node (ref "M1905") (pin "3") (pinfunction "D_3") (pintype "passive"))
      (node (ref "R1920") (pin "2") (pinfunction "2_2") (pintype "passive"))
    )
    (net (code "36") (name "Net-(M1905-G)") (class "Default")
      (node (ref "M1905") (pin "1") (pinfunction "G_1") (pintype "passive"))
      (node (ref "R1916") (pin "1") (pinfunction "1_1") (pintype "passive"))
      (node (ref "R1918") (pin "1") (pinfunction "1_1") (pintype "passive"))
    )
    (net (code "37") (name "Net-(M1906-D)") (class "Default")
      (node (ref "M1906") (pin "3") (pinfunction "D_3") (pintype "passive"))
      (node (ref "R1924") (pin "2") (pinfunction "2_2") (pintype "passive"))
    )
    (net (code "38") (name "Net-(M1906-G)") (class "Default")
      (node (ref "M1906") (pin "1") (pinfunction "G_1") (pintype "passive"))
      (node (ref "R1921") (pin "1") (pinfunction "1_1") (pintype "passive"))
      (node (ref "R1922") (pin "1") (pinfunction "1_1") (pintype "passive"))
    )
    (net (code "39") (name "Net-(M1907-D)") (class "Default")
      (node (ref "D1903") (pin "K") (pinfunction "K_K") (pintype "passive"))
      (node (ref "F1903") (pin "1") (pinfunction "1_1") (pintype "passive"))
      (node (ref "M1907") (pin "3") (pinfunction "D_3") (pintype "passive"))
      (node (ref "R1927") (pin "2") (pinfunction "2_2") (pintype "passive"))
    )
    (net (code "40") (name "Net-(M1907-G)") (class "Default")
      (node (ref "M1907") (pin "1") (pinfunction "G_1") (pintype "passive"))
      (node (ref "R1923") (pin "1") (pinfunction "1_1") (pintype "passive"))
      (node (ref "R1925") (pin "1") (pinfunction "1_1") (pintype "passive"))
    )
  )
)
